# Sima.net
KiCad netlist of a schematic drawn in Altium Designer
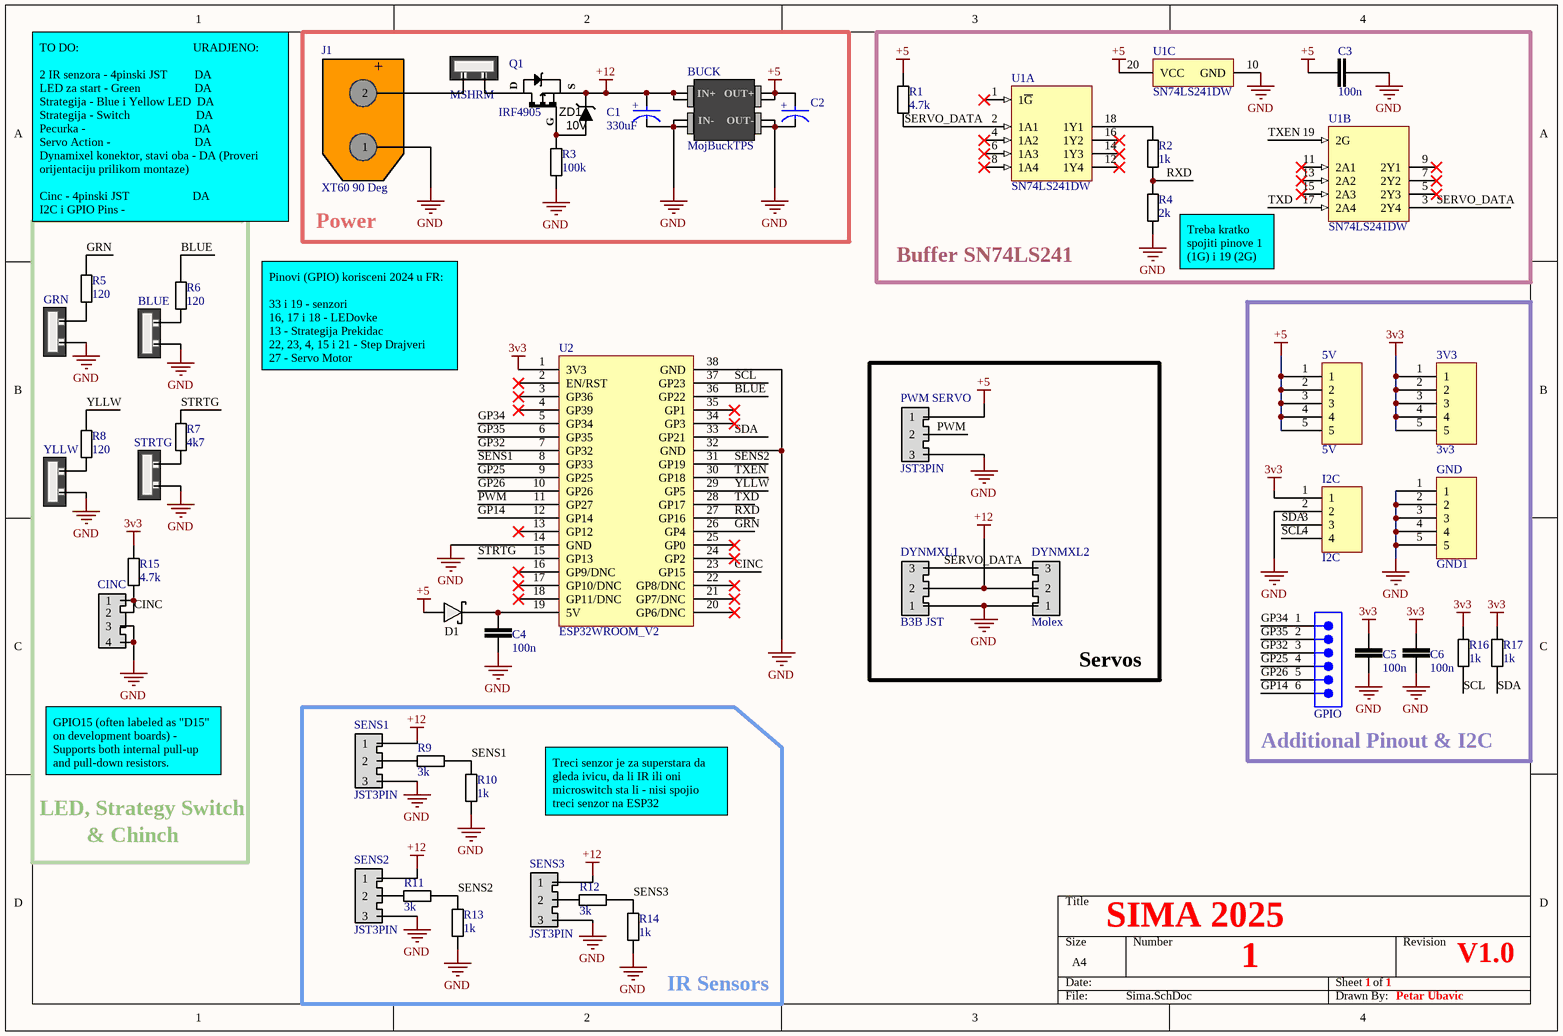
[diagram p0: Sima.SchDoc]

(export (version "E")
  (design (tool "Eeschema 10.0.6"))
  (components
    (comp (ref "3V3")
      (value "3v3")
      (footprint "PIN_HEADER5")
      (description "5 pin header 100 mil")
      (libsource (lib "SIMA") (part "PIN_HEADER5"))
    )
    (comp (ref "5V")
      (value "5V")
      (footprint "PIN_HEADER5")
      (description "5 pin header 100 mils")
      (libsource (lib "SIMA") (part "PIN_HEADER5"))
    )
    (comp (ref "BLUE")
      (value "BLUE")
      (footprint "JST2PIN")
      (description "JST 2 Pin Connector")
      (libsource (lib "Schlib") (part "JST2PIN"))
    )
    (comp (ref "BUCK")
      (value "MojBuckTPS")
      (footprint "MOJBUCKTPS_HEADER")
      (libsource (lib "Schlib") (part "MojBuckTPS"))
    )
    (comp (ref "C1")
      (value "330uF")
      (footprint "FP-OS-CON-TH-F13-d_0_6-MFG")
      (description "Conductive Polymer Aluminum Solid Capacitors (OS-CON) 330uF ±20% 25V RADIAL TH 10x13mm")
      (fields (field (name "VOLTAGE") "25V") (field (name "TOLERANCE") "20%"))
      (libsource (lib "Altium Content Vault") (part "203bc49f2ac43e59fd269a8c329ed05"))
    )
    (comp (ref "C2")
      (value "25SEPF330M+T")
      (footprint "FP-OS-CON-TH-F13-d_0_6-MFG")
      (description "Conductive Polymer Aluminum Solid Capacitors (OS-CON) 330uF ±20% 25V RADIAL TH 10x13mm")
      (fields (field (name "VOLTAGE") "25V") (field (name "TOLERANCE") "20%"))
      (libsource (lib "Altium Content Vault") (part "203bc49f2ac43e59fd269a8c329ed05"))
    )
    (comp (ref "C3")
      (value "100n")
      (footprint "CAP_0805")
      (description "CAP 100nF ±10% 50V 0805 X7R")
      (libsource (lib "") (part "C00079_1"))
    )
    (comp (ref "C4")
      (value "100n")
      (footprint "CAP_0805")
      (description "CAP 100nF ±10% 50V 0805 X7R")
      (libsource (lib "Kondezatori_Integrisano") (part "C00079"))
    )
    (comp (ref "C5")
      (value "100n")
      (footprint "CAP_0805")
      (description "CAP 100nF ±10% 50V 0805 X7R")
      (libsource (lib "Kondezatori_Integrisano") (part "C00079"))
    )
    (comp (ref "C6")
      (value "100n")
      (footprint "CAP_0805")
      (description "CAP 100nF ±10% 50V 0805 X7R")
      (libsource (lib "Kondezatori_Integrisano") (part "C00079"))
    )
    (comp (ref "CINC")
      (value "4 PIN JST XH 2.5mm pitch")
      (footprint "Connectors:JST4PIN")
      (libsource (lib "Connectors") (part "JST4PIN"))
    )
    (comp (ref "D1") (value "SCH_DIODE") (footprint "SMA") (libsource (lib "Schlib") (part "SCH_DIODE")))
    (comp (ref "DYNMXL1")
      (value "B3B JST")
      (footprint "Connectors:JST3PIN")
      (description "ST B3B-EH-A 2.5mm pitch")
      (libsource (lib "Connectors") (part "JST3PIN"))
    )
    (comp (ref "DYNMXL2")
      (value "Molex")
      (footprint "Connectors:JST3PIN")
      (description "Molex 0022035035 2.5mm pitch")
      (libsource (lib "Connectors") (part "JST3PIN"))
    )
    (comp (ref "GND")
      (value "GND1")
      (footprint "PIN_HEADER5")
      (description "5 pin header 100 mils")
      (libsource (lib "SIMA") (part "PIN_HEADER5"))
    )
    (comp (ref "GPIO")
      (value "61300611121")
      (footprint "61300611121")
      (description "WR-PHD Pin Header, THT, Vertical, pitch 2.54mm, 1 Row, 6P")
      (fields (field (name "MANUFACTURER") "Wurth Elektronik"))
      (libsource (lib "Altium_WR-PHD_rev24a") (part "61300611121"))
    )
    (comp (ref "GRN")
      (value "GRN")
      (footprint "JST2PIN")
      (description "JST 2 Pin Connector")
      (libsource (lib "Schlib") (part "JST2PIN"))
    )
    (comp (ref "I2C")
      (value "I2C")
      (footprint "UltraSonic_Sensor")
      (description "Connector onaj beli")
      (libsource (lib "SIMA") (part "UltraSonic_Sensor"))
    )
    (comp (ref "J1")
      (value "XT60 90 Deg")
      (footprint "Connectors:XT60PW-M")
      (libsource (lib "Connectors") (part "XT60PW-M"))
    )
    (comp (ref "MSHRM")
      (value "MSHRM")
      (footprint "JST2PIN")
      (description "JST 2 Pin Connector")
      (libsource (lib "") (part "JST2PIN_1"))
    )
    (comp (ref "PWM SERVO")
      (value "JST3PIN")
      (footprint "Connectors:JST3PIN")
      (description "3 PIN JST XH 2.5mm pitch")
      (libsource (lib "Connectors") (part "JST3PIN"))
    )
    (comp (ref "Q1")
      (value "IRF4905")
      (footprint "DPAK254P1524X483-3N")
      (fields
        (field (name "MANUFACTURER") "International Rectifier")
        (field (name "MANUFACTURER PART NUMBER") "IRF1404ZSPBF")
      )
      (libsource (lib "SIMA_1") (part "IRF4905"))
    )
    (comp (ref "R1")
      (value "4.7k")
      (footprint "RESISTOR_0805_SMALLSILK")
      (description "RES  4k7 OHM 1% 1/8W 0805")
      (libsource (lib "Otpornici_Integrisano") (part "R000116"))
    )
    (comp (ref "R2")
      (value "1k")
      (footprint "RESISTOR_0805_SMALLSILK")
      (description "RES  1k OHM 1% 1/8W 0805")
      (libsource (lib "Otpornici_Integrisano") (part "R000004"))
    )
    (comp (ref "R3")
      (value "100k")
      (footprint "RESISTOR_0805_SMALLSILK")
      (description "RES  100k OHM 1% 1/8W 0805")
      (libsource (lib "Otpornici_Integrisano") (part "R000006"))
    )
    (comp (ref "R4")
      (value "2k")
      (footprint "RESISTOR_0805_SMALLSILK")
      (description "RES  2k OHM 1% 1/8W 0805")
      (libsource (lib "Otpornici_Integrisano") (part "R000053"))
    )
    (comp (ref "R5")
      (value "120")
      (footprint "RESISTOR_0805_SMALLSILK")
      (description "RES  120 OHM 1% 1/8W 0805")
      (libsource (lib "Otpornici_Integrisano") (part "R000017"))
    )
    (comp (ref "R6")
      (value "120")
      (footprint "RESISTOR_0805_SMALLSILK")
      (description "RES  120 OHM 1% 1/8W 0805")
      (libsource (lib "Otpornici_Integrisano") (part "R000017"))
    )
    (comp (ref "R7")
      (value "4k7")
      (footprint "RESISTOR_0805_SMALLSILK")
      (description "RES  120 OHM 1% 1/8W 0805")
      (libsource (lib "Otpornici_Integrisano") (part "R000017"))
    )
    (comp (ref "R8")
      (value "120")
      (footprint "RESISTOR_0805_SMALLSILK")
      (description "RES  120 OHM 1% 1/8W 0805")
      (libsource (lib "Otpornici_Integrisano") (part "R000017"))
    )
    (comp (ref "R9")
      (value "3k")
      (footprint "RESISTOR_0805_SMALLSILK")
      (description "RES  3k OHM 1% 1/8W 0805")
      (libsource (lib "Otpornici_Integrisano") (part "R000081"))
    )
    (comp (ref "R10")
      (value "1k")
      (footprint "RESISTOR_0805_SMALLSILK")
      (description "RES  1k OHM 1% 1/8W 0805")
      (libsource (lib "Otpornici_Integrisano") (part "R000004"))
    )
    (comp (ref "R11")
      (value "3k")
      (footprint "RESISTOR_0805_SMALLSILK")
      (description "RES  3k OHM 1% 1/8W 0805")
      (libsource (lib "Otpornici_Integrisano") (part "R000081"))
    )
    (comp (ref "R12")
      (value "3k")
      (footprint "RESISTOR_0805_SMALLSILK")
      (description "RES  3k OHM 1% 1/8W 0805")
      (libsource (lib "Otpornici_Integrisano") (part "R000081"))
    )
    (comp (ref "R13")
      (value "1k")
      (footprint "RESISTOR_0805_SMALLSILK")
      (description "RES  1k OHM 1% 1/8W 0805")
      (libsource (lib "Otpornici_Integrisano") (part "R000004"))
    )
    (comp (ref "R14")
      (value "1k")
      (footprint "RESISTOR_0805_SMALLSILK")
      (description "RES  1k OHM 1% 1/8W 0805")
      (libsource (lib "Otpornici_Integrisano") (part "R000004"))
    )
    (comp (ref "R15")
      (value "4.7k")
      (footprint "RESISTOR_0805_SMALLSILK")
      (description "RES  4k7 OHM 1% 1/8W 0805")
      (libsource (lib "Otpornici_Integrisano") (part "R000116"))
    )
    (comp (ref "R16")
      (value "1k")
      (footprint "RESISTOR_0805_SMALLSILK")
      (description "RES  1k OHM 1% 1/8W 0805")
      (libsource (lib "Otpornici_Integrisano") (part "R000004"))
    )
    (comp (ref "R17")
      (value "1k")
      (footprint "RESISTOR_0805_SMALLSILK")
      (description "RES  1k OHM 1% 1/8W 0805")
      (libsource (lib "Otpornici_Integrisano") (part "R000004"))
    )
    (comp (ref "SENS1")
      (value "JST3PIN")
      (footprint "JST3PIN")
      (description "3 PIN JST XH 2.5mm pitch")
      (libsource (lib "Connectors") (part "JST3PIN"))
    )
    (comp (ref "SENS2")
      (value "JST3PIN")
      (footprint "JST3PIN")
      (description "3 PIN JST XH 2.5mm pitch")
      (libsource (lib "Connectors") (part "JST3PIN"))
    )
    (comp (ref "SENS3")
      (value "JST3PIN")
      (footprint "JST3PIN")
      (description "3 PIN JST XH 2.5mm pitch")
      (libsource (lib "Connectors") (part "JST3PIN"))
    )
    (comp (ref "STRTG")
      (value "STRTG")
      (footprint "JST2PIN")
      (description "JST 2 Pin Connector")
      (libsource (lib "Schlib") (part "JST2PIN"))
    )
    (comp (ref "U1")
      (value "SN74LS241DW")
      (footprint "DW0020A_N")
      (description "Octal Buffers And Line Drivers With 3-State Outputs, DW0020A, TUBE")
      (fields
        (field (name "GENERIC PART NUMBER") "SN74LS241")
        (field (name "MANUFACTURER") "Texas Instruments")
      )
      (libsource (lib "Altium Content Vault") (part "TI-SN74LS_74S241-20"))
    )
    (comp (ref "U2")
      (value "ESP32WROOM_V2")
      (footprint "ESP32WROOM")
      (description "Pinout Acine ESP32 Wroom plocice, pinovi poslagani po redu")
      (libsource (lib "SIMA") (part "ESP32WROOM_V2"))
    )
    (comp (ref "YLLW")
      (value "YLLW")
      (footprint "JST2PIN")
      (description "JST 2 Pin Connector")
      (libsource (lib "Schlib") (part "JST2PIN"))
    )
    (comp (ref "ZD1")
      (value "10V")
      (footprint "DIO_SMA")
      (description "Zener Diode 10 V 5 W ±5% Surface Mount SMC (DO-214AB)")
      (libsource (lib "SIMA_1") (part "1SMA5931-AU_R1"))
    )
  )
  (nets
    (net (code "1") (name "+5") (class "Default")
      (node (ref "5V") (pin "1") (pinfunction "1_1") (pintype "passive"))
      (node (ref "5V") (pin "2") (pinfunction "2_2") (pintype "passive"))
      (node (ref "5V") (pin "3") (pinfunction "3_3") (pintype "passive"))
      (node (ref "5V") (pin "4") (pinfunction "4_4") (pintype "passive"))
      (node (ref "5V") (pin "5") (pinfunction "5_5") (pintype "passive"))
      (node (ref "BUCK") (pin "7") (pinfunction "7_7") (pintype "passive"))
      (node (ref "BUCK") (pin "8") (pinfunction "8_8") (pintype "passive"))
      (node (ref "C2") (pin "2") (pinfunction "A_2") (pintype "passive"))
      (node (ref "C3") (pin "2") (pinfunction "2_2") (pintype "passive"))
      (node (ref "D1") (pin "1") (pinfunction "1_1") (pintype "passive"))
      (node (ref "PWM SERVO") (pin "1") (pinfunction "1_1") (pintype "passive"))
      (node (ref "R1") (pin "2") (pinfunction "2_2") (pintype "passive"))
      (node (ref "U1") (pin "20") (pinfunction "VCC_20") (pintype "power_in"))
    )
    (net (code "2") (name "+12") (class "Default")
      (node (ref "BUCK") (pin "1") (pinfunction "1_1") (pintype "passive"))
      (node (ref "BUCK") (pin "2") (pinfunction "2_2") (pintype "passive"))
      (node (ref "C1") (pin "2") (pinfunction "A_2") (pintype "passive"))
      (node (ref "DYNMXL1") (pin "2") (pinfunction "2_2") (pintype "passive"))
      (node (ref "DYNMXL2") (pin "2") (pinfunction "2_2") (pintype "passive"))
      (node (ref "Q1") (pin "3") (pinfunction "3_3") (pintype "passive"))
      (node (ref "SENS1") (pin "1") (pinfunction "1_1") (pintype "passive"))
      (node (ref "SENS2") (pin "1") (pinfunction "1_1") (pintype "passive"))
      (node (ref "SENS3") (pin "1") (pinfunction "1_1") (pintype "passive"))
      (node (ref "ZD1") (pin "1") (pinfunction "Cathode_1") (pintype "passive"))
    )
    (net (code "3") (name "/BLUE") (class "Default")
      (node (ref "R6") (pin "2") (pinfunction "2_2") (pintype "passive"))
      (node (ref "U2") (pin "36") (pinfunction "GP22_36") (pintype "passive"))
    )
    (net (code "4") (name "/CINC") (class "Default")
      (node (ref "CINC") (pin "1") (pinfunction "1_1") (pintype "passive"))
      (node (ref "CINC") (pin "2") (pinfunction "2_2") (pintype "passive"))
      (node (ref "R15") (pin "1") (pinfunction "1_1") (pintype "passive"))
      (node (ref "U2") (pin "23") (pinfunction "GP15_23") (pintype "passive"))
    )
    (net (code "5") (name "/GP14") (class "Default")
      (node (ref "GPIO") (pin "6") (pinfunction "6_6") (pintype "passive"))
      (node (ref "U2") (pin "12") (pinfunction "GP14_12") (pintype "passive"))
    )
    (net (code "6") (name "/GP25") (class "Default")
      (node (ref "GPIO") (pin "4") (pinfunction "4_4") (pintype "passive"))
      (node (ref "U2") (pin "9") (pinfunction "GP25_9") (pintype "passive"))
    )
    (net (code "7") (name "/GP26") (class "Default")
      (node (ref "GPIO") (pin "5") (pinfunction "5_5") (pintype "passive"))
      (node (ref "U2") (pin "10") (pinfunction "GP26_10") (pintype "passive"))
    )
    (net (code "8") (name "/GP32") (class "Default")
      (node (ref "GPIO") (pin "3") (pinfunction "3_3") (pintype "passive"))
      (node (ref "U2") (pin "7") (pinfunction "GP32_7") (pintype "passive"))
    )
    (net (code "9") (name "/GP34") (class "Default")
      (node (ref "GPIO") (pin "1") (pinfunction "1_1") (pintype "passive"))
      (node (ref "U2") (pin "5") (pinfunction "GP34_5") (pintype "passive"))
    )
    (net (code "10") (name "/GP35") (class "Default")
      (node (ref "GPIO") (pin "2") (pinfunction "2_2") (pintype "passive"))
      (node (ref "U2") (pin "6") (pinfunction "GP35_6") (pintype "passive"))
    )
    (net (code "11") (name "/GRN") (class "Default")
      (node (ref "R5") (pin "2") (pinfunction "2_2") (pintype "passive"))
      (node (ref "U2") (pin "26") (pinfunction "GP4_26") (pintype "passive"))
    )
    (net (code "12") (name "/PWM") (class "Default")
      (node (ref "PWM SERVO") (pin "2") (pinfunction "2_2") (pintype "passive"))
      (node (ref "U2") (pin "11") (pinfunction "GP27_11") (pintype "passive"))
    )
    (net (code "13") (name "/RXD") (class "Default")
      (node (ref "R2") (pin "1") (pinfunction "1_1") (pintype "passive"))
      (node (ref "R4") (pin "2") (pinfunction "2_2") (pintype "passive"))
      (node (ref "U2") (pin "27") (pinfunction "GP16_27") (pintype "passive"))
    )
    (net (code "14") (name "/SCL") (class "Default")
      (node (ref "I2C") (pin "4") (pinfunction "4_4") (pintype "passive"))
      (node (ref "R16") (pin "1") (pinfunction "1_1") (pintype "passive"))
      (node (ref "U2") (pin "37") (pinfunction "GP23_37") (pintype "passive"))
    )
    (net (code "15") (name "/SDA") (class "Default")
      (node (ref "I2C") (pin "3") (pinfunction "3_3") (pintype "passive"))
      (node (ref "R17") (pin "1") (pinfunction "1_1") (pintype "passive"))
      (node (ref "U2") (pin "33") (pinfunction "GP21_33") (pintype "passive"))
    )
    (net (code "16") (name "/SENS1") (class "Default")
      (node (ref "R10") (pin "2") (pinfunction "2_2") (pintype "passive"))
      (node (ref "R9") (pin "1") (pinfunction "1_1") (pintype "passive"))
      (node (ref "U2") (pin "8") (pinfunction "GP33_8") (pintype "passive"))
    )
    (net (code "17") (name "/SENS2") (class "Default")
      (node (ref "R11") (pin "1") (pinfunction "1_1") (pintype "passive"))
      (node (ref "R13") (pin "2") (pinfunction "2_2") (pintype "passive"))
      (node (ref "U2") (pin "31") (pinfunction "GP19_31") (pintype "passive"))
    )
    (net (code "18") (name "/SENS3") (class "Default")
      (node (ref "R12") (pin "1") (pinfunction "1_1") (pintype "passive"))
      (node (ref "R14") (pin "2") (pinfunction "2_2") (pintype "passive"))
    )
    (net (code "19") (name "/SERVO_DATA") (class "Default")
      (node (ref "DYNMXL1") (pin "3") (pinfunction "3_3") (pintype "passive"))
      (node (ref "DYNMXL2") (pin "3") (pinfunction "3_3") (pintype "passive"))
      (node (ref "R1") (pin "1") (pinfunction "1_1") (pintype "passive"))
      (node (ref "U1") (pin "2") (pinfunction "1A1_2") (pintype "input"))
      (node (ref "U1") (pin "3") (pinfunction "2Y4_3") (pintype "tri_state"))
    )
    (net (code "20") (name "/STRTG") (class "Default")
      (node (ref "R7") (pin "2") (pinfunction "2_2") (pintype "passive"))
      (node (ref "U2") (pin "15") (pinfunction "GP13_15") (pintype "passive"))
    )
    (net (code "21") (name "/TXD") (class "Default")
      (node (ref "U1") (pin "17") (pinfunction "2A4_17") (pintype "input"))
      (node (ref "U2") (pin "28") (pinfunction "GP17_28") (pintype "passive"))
    )
    (net (code "22") (name "/TXEN") (class "Default")
      (node (ref "U1") (pin "19") (pinfunction "2G_19") (pintype "input"))
      (node (ref "U2") (pin "30") (pinfunction "GP18_30") (pintype "passive"))
    )
    (net (code "23") (name "/YLLW") (class "Default")
      (node (ref "R8") (pin "2") (pinfunction "2_2") (pintype "passive"))
      (node (ref "U2") (pin "29") (pinfunction "GP5_29") (pintype "passive"))
    )
    (net (code "24") (name "3v3") (class "Default")
      (node (ref "3V3") (pin "1") (pinfunction "1_1") (pintype "passive"))
      (node (ref "3V3") (pin "2") (pinfunction "2_2") (pintype "passive"))
      (node (ref "3V3") (pin "3") (pinfunction "3_3") (pintype "passive"))
      (node (ref "3V3") (pin "4") (pinfunction "4_4") (pintype "passive"))
      (node (ref "3V3") (pin "5") (pinfunction "5_5") (pintype "passive"))
      (node (ref "C5") (pin "1") (pinfunction "1_1") (pintype "passive"))
      (node (ref "C6") (pin "1") (pinfunction "1_1") (pintype "passive"))
      (node (ref "I2C") (pin "1") (pinfunction "1_1") (pintype "passive"))
      (node (ref "R15") (pin "2") (pinfunction "2_2") (pintype "passive"))
      (node (ref "R16") (pin "2") (pinfunction "2_2") (pintype "passive"))
      (node (ref "R17") (pin "2") (pinfunction "2_2") (pintype "passive"))
      (node (ref "U2") (pin "1") (pinfunction "3V3_1") (pintype "passive"))
    )
    (net (code "25") (name "GND") (class "Default")
      (node (ref "BLUE") (pin "1") (pinfunction "1_1") (pintype "passive"))
      (node (ref "BUCK") (pin "3") (pinfunction "3_3") (pintype "passive"))
      (node (ref "BUCK") (pin "4") (pinfunction "4_4") (pintype "passive"))
      (node (ref "BUCK") (pin "5") (pinfunction "5_5") (pintype "passive"))
      (node (ref "BUCK") (pin "6") (pinfunction "6_6") (pintype "passive"))
      (node (ref "C1") (pin "1") (pinfunction "C_1") (pintype "passive"))
      (node (ref "C2") (pin "1") (pinfunction "C_1") (pintype "passive"))
      (node (ref "C3") (pin "1") (pinfunction "1_1") (pintype "passive"))
      (node (ref "C4") (pin "2") (pinfunction "2_2") (pintype "passive"))
      (node (ref "C5") (pin "2") (pinfunction "2_2") (pintype "passive"))
      (node (ref "C6") (pin "2") (pinfunction "2_2") (pintype "passive"))
      (node (ref "CINC") (pin "3") (pinfunction "3_3") (pintype "passive"))
      (node (ref "CINC") (pin "4") (pinfunction "4_4") (pintype "passive"))
      (node (ref "DYNMXL1") (pin "1") (pinfunction "1_1") (pintype "passive"))
      (node (ref "DYNMXL2") (pin "1") (pinfunction "1_1") (pintype "passive"))
      (node (ref "GND") (pin "1") (pinfunction "1_1") (pintype "passive"))
      (node (ref "GND") (pin "2") (pinfunction "2_2") (pintype "passive"))
      (node (ref "GND") (pin "3") (pinfunction "3_3") (pintype "passive"))
      (node (ref "GND") (pin "4") (pinfunction "4_4") (pintype "passive"))
      (node (ref "GND") (pin "5") (pinfunction "5_5") (pintype "passive"))
      (node (ref "GRN") (pin "1") (pinfunction "1_1") (pintype "passive"))
      (node (ref "I2C") (pin "2") (pinfunction "2_2") (pintype "passive"))
      (node (ref "J1") (pin "1") (pinfunction "1_1") (pintype "passive"))
      (node (ref "PWM SERVO") (pin "3") (pinfunction "3_3") (pintype "passive"))
      (node (ref "R10") (pin "1") (pinfunction "1_1") (pintype "passive"))
      (node (ref "R13") (pin "1") (pinfunction "1_1") (pintype "passive"))
      (node (ref "R14") (pin "1") (pinfunction "1_1") (pintype "passive"))
      (node (ref "R3") (pin "1") (pinfunction "1_1") (pintype "passive"))
      (node (ref "R4") (pin "1") (pinfunction "1_1") (pintype "passive"))
      (node (ref "SENS1") (pin "3") (pinfunction "3_3") (pintype "passive"))
      (node (ref "SENS2") (pin "3") (pinfunction "3_3") (pintype "passive"))
      (node (ref "SENS3") (pin "3") (pinfunction "3_3") (pintype "passive"))
      (node (ref "STRTG") (pin "1") (pinfunction "1_1") (pintype "passive"))
      (node (ref "U1") (pin "10") (pinfunction "GND_10") (pintype "power_in"))
      (node (ref "U2") (pin "14") (pinfunction "GND_14") (pintype "passive"))
      (node (ref "U2") (pin "32") (pinfunction "GND_32") (pintype "passive"))
      (node (ref "U2") (pin "38") (pinfunction "GND_38") (pintype "passive"))
      (node (ref "YLLW") (pin "1") (pinfunction "1_1") (pintype "passive"))
    )
    (net (code "26") (name "Net-(BLUE-Pad2)") (class "Default")
      (node (ref "BLUE") (pin "2") (pinfunction "2_2") (pintype "passive"))
      (node (ref "R6") (pin "1") (pinfunction "1_1") (pintype "passive"))
    )
    (net (code "27") (name "Net-(GRN-Pad2)") (class "Default")
      (node (ref "GRN") (pin "2") (pinfunction "2_2") (pintype "passive"))
      (node (ref "R5") (pin "1") (pinfunction "1_1") (pintype "passive"))
    )
    (net (code "28") (name "Net-(J1-Pad2)") (class "Default")
      (node (ref "J1") (pin "2") (pinfunction "2_2") (pintype "passive"))
      (node (ref "MSHRM") (pin "1") (pinfunction "1_1") (pintype "passive"))
    )
    (net (code "29") (name "Net-(MSHRM-Pad2)") (class "Default")
      (node (ref "MSHRM") (pin "2") (pinfunction "2_2") (pintype "passive"))
      (node (ref "Q1") (pin "4") (pinfunction "4_4") (pintype "passive"))
    )
    (net (code "30") (name "Net-(Q1-G)") (class "Default")
      (node (ref "Q1") (pin "1") (pinfunction "G_1") (pintype "passive"))
      (node (ref "R3") (pin "2") (pinfunction "2_2") (pintype "passive"))
      (node (ref "ZD1") (pin "2") (pinfunction "Anode_2") (pintype "passive"))
    )
    (net (code "31") (name "Net-(R7-Pad1)") (class "Default")
      (node (ref "R7") (pin "1") (pinfunction "1_1") (pintype "passive"))
      (node (ref "STRTG") (pin "2") (pinfunction "2_2") (pintype "passive"))
    )
    (net (code "32") (name "Net-(R8-Pad1)") (class "Default")
      (node (ref "R8") (pin "1") (pinfunction "1_1") (pintype "passive"))
      (node (ref "YLLW") (pin "2") (pinfunction "2_2") (pintype "passive"))
    )
    (net (code "33") (name "Net-(R9-Pad2)") (class "Default")
      (node (ref "R9") (pin "2") (pinfunction "2_2") (pintype "passive"))
      (node (ref "SENS1") (pin "2") (pinfunction "2_2") (pintype "passive"))
    )
    (net (code "34") (name "Net-(R11-Pad2)") (class "Default")
      (node (ref "R11") (pin "2") (pinfunction "2_2") (pintype "passive"))
      (node (ref "SENS2") (pin "2") (pinfunction "2_2") (pintype "passive"))
    )
    (net (code "35") (name "Net-(R12-Pad2)") (class "Default")
      (node (ref "R12") (pin "2") (pinfunction "2_2") (pintype "passive"))
      (node (ref "SENS3") (pin "2") (pinfunction "2_2") (pintype "passive"))
    )
    (net (code "36") (name "Net-(U1A-1Y1)") (class "Default")
      (node (ref "R2") (pin "2") (pinfunction "2_2") (pintype "passive"))
      (node (ref "U1") (pin "18") (pinfunction "1Y1_18") (pintype "tri_state"))
    )
    (net (code "37") (name "Net-(U2-5V)") (class "Default")
      (node (ref "C4") (pin "1") (pinfunction "1_1") (pintype "passive"))
      (node (ref "D1") (pin "2") (pinfunction "2_2") (pintype "passive"))
      (node (ref "U2") (pin "19") (pinfunction "5V_19") (pintype "passive"))
    )
    (net (code "38") (name "unconnected-(U1A-1A2-Pad4)") (class "Default")
      (node (ref "U1") (pin "4") (pinfunction "1A2_4") (pintype "input+no_connect"))
    )
    (net (code "39") (name "unconnected-(U1A-1A3-Pad6)") (class "Default")
      (node (ref "U1") (pin "6") (pinfunction "1A3_6") (pintype "input+no_connect"))
    )
    (net (code "40") (name "unconnected-(U1A-1A4-Pad8)") (class "Default")
      (node (ref "U1") (pin "8") (pinfunction "1A4_8") (pintype "input+no_connect"))
    )
    (net (code "41") (name "unconnected-(U1A-1Y2-Pad16)") (class "Default")
      (node (ref "U1") (pin "16") (pinfunction "1Y2_16") (pintype "tri_state+no_connect"))
    )
    (net (code "42") (name "unconnected-(U1A-1Y3-Pad14)") (class "Default")
      (node (ref "U1") (pin "14") (pinfunction "1Y3_14") (pintype "tri_state+no_connect"))
    )
    (net (code "43") (name "unconnected-(U1A-1Y4-Pad12)") (class "Default")
      (node (ref "U1") (pin "12") (pinfunction "1Y4_12") (pintype "tri_state+no_connect"))
    )
    (net (code "44") (name "unconnected-(U1A-1~{G}-Pad1)") (class "Default")
      (node (ref "U1") (pin "1") (pinfunction "1~{G}_1") (pintype "input+no_connect"))
    )
    (net (code "45") (name "unconnected-(U1B-2A1-Pad11)") (class "Default")
      (node (ref "U1") (pin "11") (pinfunction "2A1_11") (pintype "input+no_connect"))
    )
    (net (code "46") (name "unconnected-(U1B-2A2-Pad13)") (class "Default")
      (node (ref "U1") (pin "13") (pinfunction "2A2_13") (pintype "input+no_connect"))
    )
    (net (code "47") (name "unconnected-(U1B-2A3-Pad15)") (class "Default")
      (node (ref "U1") (pin "15") (pinfunction "2A3_15") (pintype "input+no_connect"))
    )
    (net (code "48") (name "unconnected-(U1B-2Y1-Pad9)") (class "Default")
      (node (ref "U1") (pin "9") (pinfunction "2Y1_9") (pintype "tri_state+no_connect"))
    )
    (net (code "49") (name "unconnected-(U1B-2Y2-Pad7)") (class "Default")
      (node (ref "U1") (pin "7") (pinfunction "2Y2_7") (pintype "tri_state+no_connect"))
    )
    (net (code "50") (name "unconnected-(U1B-2Y3-Pad5)") (class "Default")
      (node (ref "U1") (pin "5") (pinfunction "2Y3_5") (pintype "tri_state+no_connect"))
    )
    (net (code "51") (name "unconnected-(U2-EN{slash}RST-Pad2)") (class "Default")
      (node (ref "U2") (pin "2") (pinfunction "EN/RST_2") (pintype "passive+no_connect"))
    )
    (net (code "52") (name "unconnected-(U2-GP0-Pad25)") (class "Default")
      (node (ref "U2") (pin "25") (pinfunction "GP0_25") (pintype "passive+no_connect"))
    )
    (net (code "53") (name "unconnected-(U2-GP1-Pad35)") (class "Default")
      (node (ref "U2") (pin "35") (pinfunction "GP1_35") (pintype "passive+no_connect"))
    )
    (net (code "54") (name "unconnected-(U2-GP2-Pad24)") (class "Default")
      (node (ref "U2") (pin "24") (pinfunction "GP2_24") (pintype "passive+no_connect"))
    )
    (net (code "55") (name "unconnected-(U2-GP3-Pad34)") (class "Default")
      (node (ref "U2") (pin "34") (pinfunction "GP3_34") (pintype "passive+no_connect"))
    )
    (net (code "56") (name "unconnected-(U2-GP6{slash}DNC-Pad20)") (class "Default")
      (node (ref "U2") (pin "20") (pinfunction "GP6/DNC_20") (pintype "passive+no_connect"))
    )
    (net (code "57") (name "unconnected-(U2-GP7{slash}DNC-Pad21)") (class "Default")
      (node (ref "U2") (pin "21") (pinfunction "GP7/DNC_21") (pintype "passive+no_connect"))
    )
    (net (code "58") (name "unconnected-(U2-GP8{slash}DNC-Pad22)") (class "Default")
      (node (ref "U2") (pin "22") (pinfunction "GP8/DNC_22") (pintype "passive+no_connect"))
    )
    (net (code "59") (name "unconnected-(U2-GP9{slash}DNC-Pad16)") (class "Default")
      (node (ref "U2") (pin "16") (pinfunction "GP9/DNC_16") (pintype "passive+no_connect"))
    )
    (net (code "60") (name "unconnected-(U2-GP10{slash}DNC-Pad17)") (class "Default")
      (node (ref "U2") (pin "17") (pinfunction "GP10/DNC_17") (pintype "passive+no_connect"))
    )
    (net (code "61") (name "unconnected-(U2-GP11{slash}DNC-Pad18)") (class "Default")
      (node (ref "U2") (pin "18") (pinfunction "GP11/DNC_18") (pintype "passive+no_connect"))
    )
    (net (code "62") (name "unconnected-(U2-GP12-Pad13)") (class "Default")
      (node (ref "U2") (pin "13") (pinfunction "GP12_13") (pintype "passive+no_connect"))
    )
    (net (code "63") (name "unconnected-(U2-GP36-Pad3)") (class "Default")
      (node (ref "U2") (pin "3") (pinfunction "GP36_3") (pintype "passive+no_connect"))
    )
    (net (code "64") (name "unconnected-(U2-GP39-Pad4)") (class "Default")
      (node (ref "U2") (pin "4") (pinfunction "GP39_4") (pintype "passive+no_connect"))
    )
  )
)
